# Colibri.net
KiCad netlist of a schematic drawn in Altium Designer
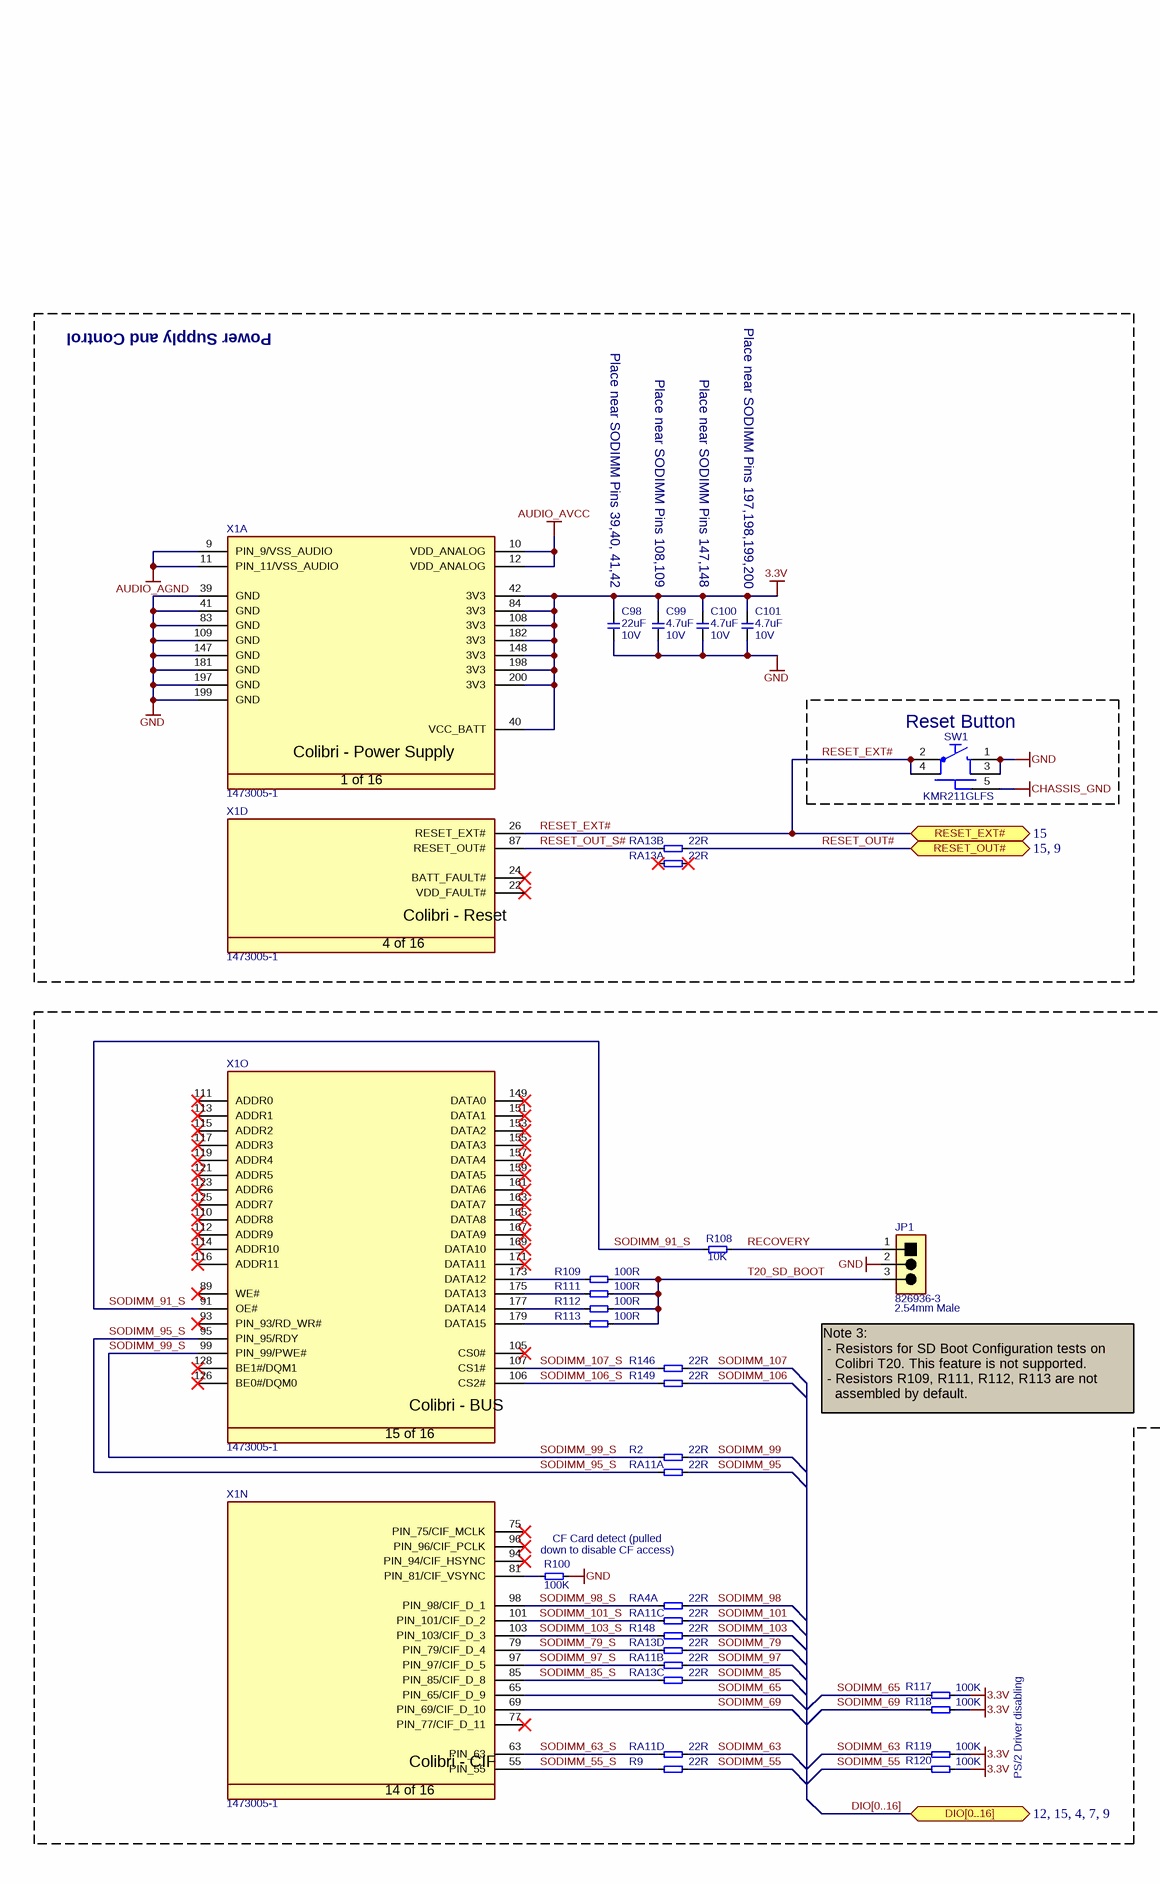
[diagram p0: Colibri.SchDoc, left]
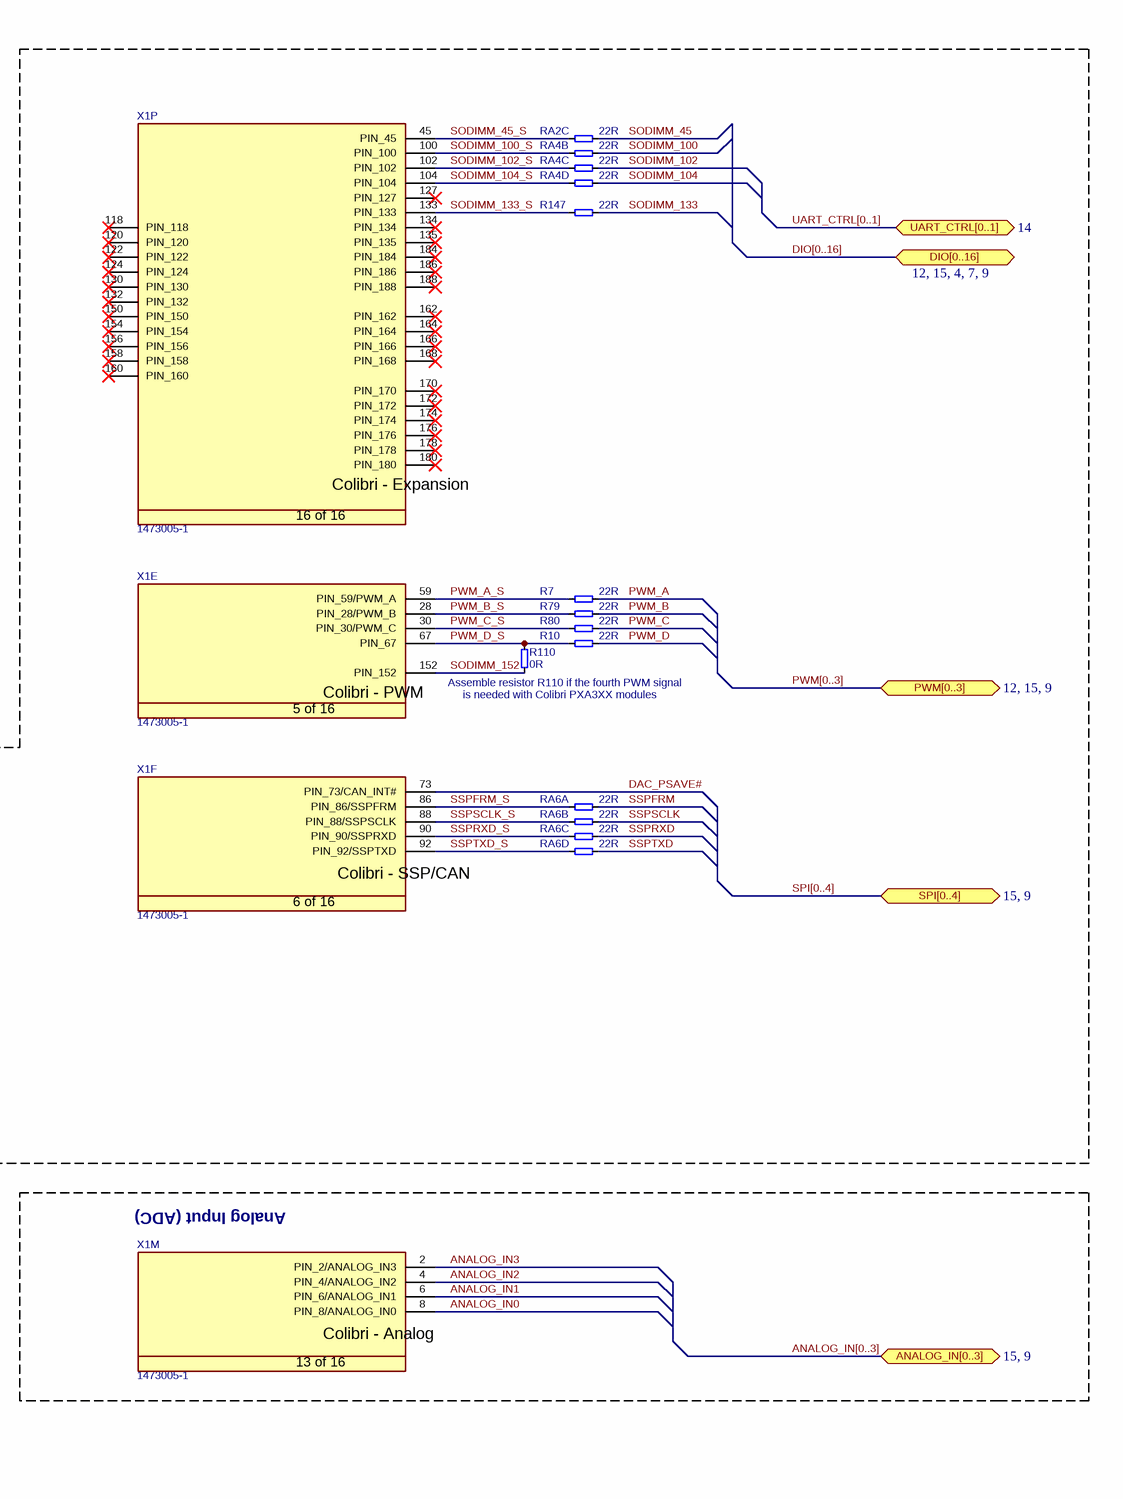
[diagram p1: Colibri.SchDoc, right]

(export (version "E")
  (design (tool "Eeschema 10.0.6"))
  (components
    (comp (ref "C98")
      (value "22uF")
      (footprint "T_CAPC0805X125N")
      (description "Capacitor Ceramic X5R 22uF 10V 20% 0805")
      (fields (field (name "TOLERANCE") "20%") (field (name "RATING") "10V"))
      (libsource (lib "Iris") (part "C-X5R-22uF-10V-20%-0805"))
    )
    (comp (ref "C99")
      (value "4.7uF")
      (footprint "T_CAPC0603X33N")
      (description "Capacitor Ceramic X5R 4.7uF 10V 10% 0603")
      (fields (field (name "TOLERANCE") "10%") (field (name "RATING") "10V"))
      (libsource (lib "Iris") (part "C-X5R-4.7uF-10V-10%-0603"))
    )
    (comp (ref "C100")
      (value "4.7uF")
      (footprint "T_CAPC0603X33N")
      (description "Capacitor Ceramic X5R 4.7uF 10V 10% 0603")
      (fields (field (name "TOLERANCE") "10%") (field (name "RATING") "10V"))
      (libsource (lib "Iris") (part "C-X5R-4.7uF-10V-10%-0603"))
    )
    (comp (ref "C101")
      (value "4.7uF")
      (footprint "T_CAPC0603X33N")
      (description "Capacitor Ceramic X5R 4.7uF 10V 10% 0603")
      (fields (field (name "TOLERANCE") "10%") (field (name "RATING") "10V"))
      (libsource (lib "Iris") (part "C-X5R-4.7uF-10V-10%-0603"))
    )
    (comp (ref "JP1")
      (value "826936-3")
      (footprint "T_TYCO_826936-3")
      (description "Jumper, 3-Pin")
      (fields (field (name "MANUFACTURER PART NO.") "826936-3"))
      (libsource (lib "Iris") (part "CON-Tyco-826936-3-1X3-2.54mm-JP"))
    )
    (comp (ref "R2")
      (value "22R")
      (footprint "RESC1005X40N")
      (description "Resistor 22 ohm 63mW 5% 0402")
      (fields (field (name "TOLERANCE") "5%"))
      (libsource (lib "Iris") (part "R-22R-63mW-5%-0402"))
    )
    (comp (ref "R7")
      (value "22R")
      (footprint "RESC1005X40N")
      (description "Resistor 22 ohm 63mW 5% 0402")
      (fields (field (name "TOLERANCE") "5%"))
      (libsource (lib "Iris") (part "R-22R-63mW-5%-0402"))
    )
    (comp (ref "R9")
      (value "22R")
      (footprint "RESC1005X40N")
      (description "Resistor 22 ohm 63mW 5% 0402")
      (fields (field (name "TOLERANCE") "5%"))
      (libsource (lib "Iris") (part "R-22R-63mW-5%-0402"))
    )
    (comp (ref "R10")
      (value "22R")
      (footprint "RESC1005X40N")
      (description "Resistor 22 ohm 63mW 5% 0402")
      (fields (field (name "TOLERANCE") "5%"))
      (libsource (lib "Iris") (part "R-22R-63mW-5%-0402"))
    )
    (comp (ref "R79")
      (value "22R")
      (footprint "RESC1005X40N")
      (description "Resistor 22 ohm 63mW 5% 0402")
      (fields (field (name "TOLERANCE") "5%"))
      (libsource (lib "Iris") (part "R-22R-63mW-5%-0402"))
    )
    (comp (ref "R80")
      (value "22R")
      (footprint "RESC1005X40N")
      (description "Resistor 22 ohm 63mW 5% 0402")
      (fields (field (name "TOLERANCE") "5%"))
      (libsource (lib "Iris") (part "R-22R-63mW-5%-0402"))
    )
    (comp (ref "R100")
      (value "100K")
      (footprint "RESC1005X40N")
      (description "Resistor 100 Kohm 63mW 5% 0402")
      (fields (field (name "TOLERANCE") "5%"))
      (libsource (lib "Iris") (part "R-100KR-63mW-5%-0402"))
    )
    (comp (ref "R108")
      (value "10K")
      (footprint "RESC1005X40N")
      (description "Resistor 10 Kohm 63mW 1% 0402")
      (fields (field (name "TOLERANCE") "1%"))
      (libsource (lib "Iris") (part "R-10KR-63mW-1%-0402"))
    )
    (comp (ref "R109")
      (value "100R")
      (footprint "T_RESC0603X30N")
      (description "Resistor 100 ohm 63mW 5% 0603")
      (fields (field (name "TOLERANCE") "5%"))
      (libsource (lib "Iris") (part "R-100R-63mW-5%-0603"))
    )
    (comp (ref "R110")
      (value "0R")
      (footprint "T_RESC0603X30N")
      (description "Resistor 0 ohm 63mW 5% 0603")
      (fields (field (name "TOLERANCE") "5%"))
      (libsource (lib "Iris") (part "R-0R-63mW-5%-0603"))
    )
    (comp (ref "R111")
      (value "100R")
      (footprint "T_RESC0603X30N")
      (description "Resistor 100 ohm 63mW 5% 0603")
      (fields (field (name "TOLERANCE") "5%"))
      (libsource (lib "Iris") (part "R-100R-63mW-5%-0603"))
    )
    (comp (ref "R112")
      (value "100R")
      (footprint "T_RESC0603X30N")
      (description "Resistor 100 ohm 63mW 5% 0603")
      (fields (field (name "TOLERANCE") "5%"))
      (libsource (lib "Iris") (part "R-100R-63mW-5%-0603"))
    )
    (comp (ref "R113")
      (value "100R")
      (footprint "T_RESC0603X30N")
      (description "Resistor 100 ohm 63mW 5% 0603")
      (fields (field (name "TOLERANCE") "5%"))
      (libsource (lib "Iris") (part "R-100R-63mW-5%-0603"))
    )
    (comp (ref "R117")
      (value "100K")
      (footprint "RESC1005X40N")
      (description "Resistor 100 Kohm 63mW 5% 0402")
      (fields (field (name "TOLERANCE") "5%"))
      (libsource (lib "Iris") (part "R-100KR-63mW-5%-0402"))
    )
    (comp (ref "R118")
      (value "100K")
      (footprint "RESC1005X40N")
      (description "Resistor 100 Kohm 63mW 5% 0402")
      (fields (field (name "TOLERANCE") "5%"))
      (libsource (lib "Iris") (part "R-100KR-63mW-5%-0402"))
    )
    (comp (ref "R119")
      (value "100K")
      (footprint "RESC1005X40N")
      (description "Resistor 100 Kohm 63mW 5% 0402")
      (fields (field (name "TOLERANCE") "5%"))
      (libsource (lib "Iris") (part "R-100KR-63mW-5%-0402"))
    )
    (comp (ref "R120")
      (value "100K")
      (footprint "RESC1005X40N")
      (description "Resistor 100 Kohm 63mW 5% 0402")
      (fields (field (name "TOLERANCE") "5%"))
      (libsource (lib "Iris") (part "R-100KR-63mW-5%-0402"))
    )
    (comp (ref "R146")
      (value "22R")
      (footprint "RESC1005X40N")
      (description "Resistor 22 ohm 63mW 5% 0402")
      (fields (field (name "TOLERANCE") "5%"))
      (libsource (lib "Iris") (part "R-22R-63mW-5%-0402"))
    )
    (comp (ref "R147")
      (value "22R")
      (footprint "RESC1005X40N")
      (description "Resistor 22 ohm 63mW 5% 0402")
      (fields (field (name "TOLERANCE") "5%"))
      (libsource (lib "Iris") (part "R-22R-63mW-5%-0402"))
    )
    (comp (ref "R148")
      (value "22R")
      (footprint "RESC1005X40N")
      (description "Resistor 22 ohm 63mW 5% 0402")
      (fields (field (name "TOLERANCE") "5%"))
      (libsource (lib "Iris") (part "R-22R-63mW-5%-0402"))
    )
    (comp (ref "R149")
      (value "22R")
      (footprint "RESC1005X40N")
      (description "Resistor 22 ohm 63mW 5% 0402")
      (fields (field (name "TOLERANCE") "5%"))
      (libsource (lib "Iris") (part "R-22R-63mW-5%-0402"))
    )
    (comp (ref "RA2")
      (value "22R")
      (footprint "T_Resistor_Array_X4")
      (description "Resistor Array 22 R 63mW 5% 1206")
      (fields (field (name "TOLERANCE") "5%"))
      (libsource (lib "Iris") (part "RA-22R-63mW-5%-1206-div"))
    )
    (comp (ref "RA4")
      (value "22R")
      (footprint "T_Resistor_Array_X4")
      (description "Resistor Array 22 R 63mW 5% 1206")
      (fields (field (name "TOLERANCE") "5%"))
      (libsource (lib "Iris") (part "RA-22R-63mW-5%-1206-div"))
    )
    (comp (ref "RA6")
      (value "22R")
      (footprint "T_Resistor_Array_X4")
      (description "Resistor Array 22 R 63mW 5% 1206")
      (fields (field (name "TOLERANCE") "5%"))
      (libsource (lib "Iris") (part "RA-22R-63mW-5%-1206-div"))
    )
    (comp (ref "RA11")
      (value "22R")
      (footprint "T_Resistor_Array_X4")
      (description "Resistor Array 22 R 63mW 5% 1206")
      (fields (field (name "TOLERANCE") "5%"))
      (libsource (lib "Iris") (part "RA-22R-63mW-5%-1206-div"))
    )
    (comp (ref "RA13")
      (value "22R")
      (footprint "T_Resistor_Array_X4")
      (description "Resistor Array 22 R 63mW 5% 1206")
      (fields (field (name "TOLERANCE") "5%"))
      (libsource (lib "Iris") (part "RA-22R-63mW-5%-1206-div"))
    )
    (comp (ref "SW1")
      (value "KMR211GLFS")
      (footprint "T_CnK_KMR211GLFS")
      (description "Power ON Switch")
      (libsource (lib "Iris") (part "SW_CnK-KMR211GLFS-1VA"))
    )
    (comp (ref "X1")
      (value "1473005-1")
      (footprint "T_Tyco_1473005-1")
      (description "SODIMM Connector")
      (fields (field (name "MANUFACTURER PART NO.") "1473005-1"))
      (libsource (lib "Iris") (part "CON-Tyco-1473005-1-200-0.6mm"))
    )
  )
  (nets
    (net (code "29") (name "/ANALOG_IN0") (class "Default")
      (node (ref "X1") (pin "8") (pinfunction "PIN_8/ANALOG_IN0_8") (pintype "passive"))
    )
    (net (code "30") (name "/ANALOG_IN1") (class "Default")
      (node (ref "X1") (pin "6") (pinfunction "PIN_6/ANALOG_IN1_6") (pintype "passive"))
    )
    (net (code "31") (name "/ANALOG_IN2") (class "Default")
      (node (ref "X1") (pin "4") (pinfunction "PIN_4/ANALOG_IN2_4") (pintype "passive"))
    )
    (net (code "32") (name "/ANALOG_IN3") (class "Default")
      (node (ref "X1") (pin "2") (pinfunction "PIN_2/ANALOG_IN3_2") (pintype "passive"))
    )
    (net (code "34") (name "/DAC_PSAVE#") (class "Default")
      (node (ref "X1") (pin "73") (pinfunction "PIN_73/CAN_INT#_73") (pintype "passive"))
    )
    (net (code "37") (name "/PWM_A") (class "Default")
      (node (ref "R7") (pin "2") (pinfunction "2_2") (pintype "passive"))
    )
    (net (code "38") (name "/PWM_A_S") (class "Default")
      (node (ref "R7") (pin "1") (pinfunction "1_1") (pintype "passive"))
      (node (ref "X1") (pin "59") (pinfunction "PIN_59/PWM_A_59") (pintype "passive"))
    )
    (net (code "39") (name "/PWM_B") (class "Default")
      (node (ref "R79") (pin "2") (pinfunction "2_2") (pintype "passive"))
    )
    (net (code "40") (name "/PWM_B_S") (class "Default")
      (node (ref "R79") (pin "1") (pinfunction "1_1") (pintype "passive"))
      (node (ref "X1") (pin "28") (pinfunction "PIN_28/PWM_B_28") (pintype "passive"))
    )
    (net (code "41") (name "/PWM_C") (class "Default")
      (node (ref "R80") (pin "2") (pinfunction "2_2") (pintype "passive"))
    )
    (net (code "42") (name "/PWM_C_S") (class "Default")
      (node (ref "R80") (pin "1") (pinfunction "1_1") (pintype "passive"))
      (node (ref "X1") (pin "30") (pinfunction "PIN_30/PWM_C_30") (pintype "passive"))
    )
    (net (code "43") (name "/PWM_D") (class "Default")
      (node (ref "R10") (pin "2") (pinfunction "2_2") (pintype "passive"))
    )
    (net (code "44") (name "/PWM_D_S") (class "Default")
      (node (ref "R10") (pin "1") (pinfunction "1_1") (pintype "passive"))
      (node (ref "R110") (pin "1") (pinfunction "1_1") (pintype "passive"))
      (node (ref "X1") (pin "67") (pinfunction "PIN_67_67") (pintype "passive"))
    )
    (net (code "45") (name "/RECOVERY") (class "Default")
      (node (ref "JP1") (pin "1") (pinfunction "1_1") (pintype "passive"))
      (node (ref "R108") (pin "2") (pinfunction "2_2") (pintype "passive"))
    )
    (net (code "46") (name "/RESET_EXT#") (class "Default")
      (node (ref "SW1") (pin "2") (pinfunction "2_2") (pintype "passive"))
      (node (ref "SW1") (pin "4") (pinfunction "4_4") (pintype "passive"))
      (node (ref "X1") (pin "26") (pinfunction "RESET_EXT#_26") (pintype "passive"))
    )
    (net (code "47") (name "/RESET_OUT#") (class "Default")
      (node (ref "RA13") (pin "6") (pinfunction "6_6") (pintype "passive"))
    )
    (net (code "48") (name "/RESET_OUT_S#") (class "Default")
      (node (ref "RA13") (pin "2") (pinfunction "2_2") (pintype "passive"))
      (node (ref "X1") (pin "87") (pinfunction "RESET_OUT#_87") (pintype "passive"))
    )
    (net (code "49") (name "/SODIMM_45") (class "Default")
      (node (ref "RA2") (pin "7") (pinfunction "7_7") (pintype "passive"))
    )
    (net (code "50") (name "/SODIMM_45_S") (class "Default")
      (node (ref "RA2") (pin "3") (pinfunction "3_3") (pintype "passive"))
      (node (ref "X1") (pin "45") (pinfunction "PIN_45_45") (pintype "passive"))
    )
    (net (code "51") (name "/SODIMM_55") (class "Default")
      (node (ref "R120") (pin "2") (pinfunction "2_2") (pintype "passive"))
      (node (ref "R9") (pin "2") (pinfunction "2_2") (pintype "passive"))
    )
    (net (code "52") (name "/SODIMM_55_S") (class "Default")
      (node (ref "R9") (pin "1") (pinfunction "1_1") (pintype "passive"))
      (node (ref "X1") (pin "55") (pinfunction "PIN_55_55") (pintype "passive"))
    )
    (net (code "53") (name "/SODIMM_63") (class "Default")
      (node (ref "R119") (pin "2") (pinfunction "2_2") (pintype "passive"))
      (node (ref "RA11") (pin "8") (pinfunction "8_8") (pintype "passive"))
    )
    (net (code "54") (name "/SODIMM_63_S") (class "Default")
      (node (ref "RA11") (pin "4") (pinfunction "4_4") (pintype "passive"))
      (node (ref "X1") (pin "63") (pinfunction "PIN_63_63") (pintype "passive"))
    )
    (net (code "55") (name "/SODIMM_65") (class "Default")
      (node (ref "R117") (pin "2") (pinfunction "2_2") (pintype "passive"))
      (node (ref "X1") (pin "65") (pinfunction "PIN_65/CIF_D_9_65") (pintype "passive"))
    )
    (net (code "56") (name "/SODIMM_69") (class "Default")
      (node (ref "R118") (pin "2") (pinfunction "2_2") (pintype "passive"))
      (node (ref "X1") (pin "69") (pinfunction "PIN_69/CIF_D_10_69") (pintype "passive"))
    )
    (net (code "57") (name "/SODIMM_79") (class "Default")
      (node (ref "RA13") (pin "8") (pinfunction "8_8") (pintype "passive"))
    )
    (net (code "58") (name "/SODIMM_79_S") (class "Default")
      (node (ref "RA13") (pin "4") (pinfunction "4_4") (pintype "passive"))
      (node (ref "X1") (pin "79") (pinfunction "PIN_79/CIF_D_4_79") (pintype "passive"))
    )
    (net (code "59") (name "/SODIMM_85") (class "Default")
      (node (ref "RA13") (pin "7") (pinfunction "7_7") (pintype "passive"))
    )
    (net (code "60") (name "/SODIMM_85_S") (class "Default")
      (node (ref "RA13") (pin "3") (pinfunction "3_3") (pintype "passive"))
      (node (ref "X1") (pin "85") (pinfunction "PIN_85/CIF_D_8_85") (pintype "passive"))
    )
    (net (code "61") (name "/SODIMM_91_S") (class "Default")
      (node (ref "R108") (pin "1") (pinfunction "1_1") (pintype "passive"))
      (node (ref "X1") (pin "91") (pinfunction "OE#_91") (pintype "passive"))
    )
    (net (code "62") (name "/SODIMM_95") (class "Default")
      (node (ref "RA11") (pin "5") (pinfunction "5_5") (pintype "passive"))
    )
    (net (code "63") (name "/SODIMM_95_S") (class "Default")
      (node (ref "RA11") (pin "1") (pinfunction "1_1") (pintype "passive"))
      (node (ref "X1") (pin "95") (pinfunction "PIN_95/RDY_95") (pintype "passive"))
    )
    (net (code "64") (name "/SODIMM_97") (class "Default")
      (node (ref "RA11") (pin "6") (pinfunction "6_6") (pintype "passive"))
    )
    (net (code "65") (name "/SODIMM_97_S") (class "Default")
      (node (ref "RA11") (pin "2") (pinfunction "2_2") (pintype "passive"))
      (node (ref "X1") (pin "97") (pinfunction "PIN_97/CIF_D_5_97") (pintype "passive"))
    )
    (net (code "66") (name "/SODIMM_98") (class "Default")
      (node (ref "RA4") (pin "5") (pinfunction "5_5") (pintype "passive"))
    )
    (net (code "67") (name "/SODIMM_98_S") (class "Default")
      (node (ref "RA4") (pin "1") (pinfunction "1_1") (pintype "passive"))
      (node (ref "X1") (pin "98") (pinfunction "PIN_98/CIF_D_1_98") (pintype "passive"))
    )
    (net (code "68") (name "/SODIMM_99") (class "Default")
      (node (ref "R2") (pin "2") (pinfunction "2_2") (pintype "passive"))
    )
    (net (code "69") (name "/SODIMM_99_S") (class "Default")
      (node (ref "R2") (pin "1") (pinfunction "1_1") (pintype "passive"))
      (node (ref "X1") (pin "99") (pinfunction "PIN_99/PWE#_99") (pintype "passive"))
    )
    (net (code "70") (name "/SODIMM_100") (class "Default")
      (node (ref "RA4") (pin "6") (pinfunction "6_6") (pintype "passive"))
    )
    (net (code "71") (name "/SODIMM_100_S") (class "Default")
      (node (ref "RA4") (pin "2") (pinfunction "2_2") (pintype "passive"))
      (node (ref "X1") (pin "100") (pinfunction "PIN_100_100") (pintype "passive"))
    )
    (net (code "72") (name "/SODIMM_101") (class "Default")
      (node (ref "RA11") (pin "7") (pinfunction "7_7") (pintype "passive"))
    )
    (net (code "73") (name "/SODIMM_101_S") (class "Default")
      (node (ref "RA11") (pin "3") (pinfunction "3_3") (pintype "passive"))
      (node (ref "X1") (pin "101") (pinfunction "PIN_101/CIF_D_2_101") (pintype "passive"))
    )
    (net (code "74") (name "/SODIMM_102") (class "Default")
      (node (ref "RA4") (pin "7") (pinfunction "7_7") (pintype "passive"))
    )
    (net (code "75") (name "/SODIMM_102_S") (class "Default")
      (node (ref "RA4") (pin "3") (pinfunction "3_3") (pintype "passive"))
      (node (ref "X1") (pin "102") (pinfunction "PIN_102_102") (pintype "passive"))
    )
    (net (code "76") (name "/SODIMM_103") (class "Default")
      (node (ref "R148") (pin "2") (pinfunction "2_2") (pintype "passive"))
    )
    (net (code "77") (name "/SODIMM_103_S") (class "Default")
      (node (ref "R148") (pin "1") (pinfunction "1_1") (pintype "passive"))
      (node (ref "X1") (pin "103") (pinfunction "PIN_103/CIF_D_3_103") (pintype "passive"))
    )
    (net (code "78") (name "/SODIMM_104") (class "Default")
      (node (ref "RA4") (pin "8") (pinfunction "8_8") (pintype "passive"))
    )
    (net (code "79") (name "/SODIMM_104_S") (class "Default")
      (node (ref "RA4") (pin "4") (pinfunction "4_4") (pintype "passive"))
      (node (ref "X1") (pin "104") (pinfunction "PIN_104_104") (pintype "passive"))
    )
    (net (code "80") (name "/SODIMM_106") (class "Default")
      (node (ref "R149") (pin "2") (pinfunction "2_2") (pintype "passive"))
    )
    (net (code "81") (name "/SODIMM_106_S") (class "Default")
      (node (ref "R149") (pin "1") (pinfunction "1_1") (pintype "passive"))
      (node (ref "X1") (pin "106") (pinfunction "CS2#_106") (pintype "passive"))
    )
    (net (code "82") (name "/SODIMM_107") (class "Default")
      (node (ref "R146") (pin "2") (pinfunction "2_2") (pintype "passive"))
    )
    (net (code "83") (name "/SODIMM_107_S") (class "Default")
      (node (ref "R146") (pin "1") (pinfunction "1_1") (pintype "passive"))
      (node (ref "X1") (pin "107") (pinfunction "CS1#_107") (pintype "passive"))
    )
    (net (code "84") (name "/SODIMM_133") (class "Default")
      (node (ref "R147") (pin "2") (pinfunction "2_2") (pintype "passive"))
    )
    (net (code "85") (name "/SODIMM_133_S") (class "Default")
      (node (ref "R147") (pin "1") (pinfunction "1_1") (pintype "passive"))
      (node (ref "X1") (pin "133") (pinfunction "PIN_133_133") (pintype "passive"))
    )
    (net (code "86") (name "/SODIMM_152") (class "Default")
      (node (ref "R110") (pin "2") (pinfunction "2_2") (pintype "passive"))
      (node (ref "X1") (pin "152") (pinfunction "PIN_152_152") (pintype "passive"))
    )
    (net (code "88") (name "/SSPFRM") (class "Default")
      (node (ref "RA6") (pin "5") (pinfunction "5_5") (pintype "passive"))
    )
    (net (code "89") (name "/SSPFRM_S") (class "Default")
      (node (ref "RA6") (pin "1") (pinfunction "1_1") (pintype "passive"))
      (node (ref "X1") (pin "86") (pinfunction "PIN_86/SSPFRM_86") (pintype "passive"))
    )
    (net (code "90") (name "/SSPRXD") (class "Default")
      (node (ref "RA6") (pin "7") (pinfunction "7_7") (pintype "passive"))
    )
    (net (code "91") (name "/SSPRXD_S") (class "Default")
      (node (ref "RA6") (pin "3") (pinfunction "3_3") (pintype "passive"))
      (node (ref "X1") (pin "90") (pinfunction "PIN_90/SSPRXD_90") (pintype "passive"))
    )
    (net (code "92") (name "/SSPSCLK") (class "Default")
      (node (ref "RA6") (pin "6") (pinfunction "6_6") (pintype "passive"))
    )
    (net (code "93") (name "/SSPSCLK_S") (class "Default")
      (node (ref "RA6") (pin "2") (pinfunction "2_2") (pintype "passive"))
      (node (ref "X1") (pin "88") (pinfunction "PIN_88/SSPSCLK_88") (pintype "passive"))
    )
    (net (code "94") (name "/SSPTXD") (class "Default")
      (node (ref "RA6") (pin "8") (pinfunction "8_8") (pintype "passive"))
    )
    (net (code "95") (name "/SSPTXD_S") (class "Default")
      (node (ref "RA6") (pin "4") (pinfunction "4_4") (pintype "passive"))
      (node (ref "X1") (pin "92") (pinfunction "PIN_92/SSPTXD_92") (pintype "passive"))
    )
    (net (code "96") (name "/T20_SD_BOOT") (class "Default")
      (node (ref "JP1") (pin "3") (pinfunction "3_3") (pintype "passive"))
      (node (ref "R109") (pin "1") (pinfunction "1_1") (pintype "passive"))
      (node (ref "R111") (pin "1") (pinfunction "1_1") (pintype "passive"))
      (node (ref "R112") (pin "1") (pinfunction "1_1") (pintype "passive"))
      (node (ref "R113") (pin "1") (pinfunction "1_1") (pintype "passive"))
    )
    (net (code "98") (name "3.3V") (class "Default")
      (node (ref "C100") (pin "1") (pinfunction "1_1") (pintype "passive"))
      (node (ref "C101") (pin "1") (pinfunction "1_1") (pintype "passive"))
      (node (ref "C98") (pin "2") (pinfunction "2_2") (pintype "passive"))
      (node (ref "C99") (pin "1") (pinfunction "1_1") (pintype "passive"))
      (node (ref "R117") (pin "1") (pinfunction "1_1") (pintype "passive"))
      (node (ref "R118") (pin "1") (pinfunction "1_1") (pintype "passive"))
      (node (ref "R119") (pin "1") (pinfunction "1_1") (pintype "passive"))
      (node (ref "R120") (pin "1") (pinfunction "1_1") (pintype "passive"))
      (node (ref "X1") (pin "108") (pinfunction "3V3_108") (pintype "passive"))
      (node (ref "X1") (pin "148") (pinfunction "3V3_148") (pintype "passive"))
      (node (ref "X1") (pin "182") (pinfunction "3V3_182") (pintype "power_in"))
      (node (ref "X1") (pin "198") (pinfunction "3V3_198") (pintype "power_in"))
      (node (ref "X1") (pin "200") (pinfunction "3V3_200") (pintype "power_in"))
      (node (ref "X1") (pin "40") (pinfunction "VCC_BATT_40") (pintype "power_in"))
      (node (ref "X1") (pin "42") (pinfunction "3V3_42") (pintype "power_in"))
      (node (ref "X1") (pin "84") (pinfunction "3V3_84") (pintype "power_in"))
    )
    (net (code "99") (name "AUDIO_AGND") (class "Default")
      (node (ref "X1") (pin "11") (pinfunction "PIN_11/VSS_AUDIO_11") (pintype "passive"))
      (node (ref "X1") (pin "9") (pinfunction "PIN_9/VSS_AUDIO_9") (pintype "passive"))
    )
    (net (code "100") (name "AUDIO_AVCC") (class "Default")
      (node (ref "X1") (pin "10") (pinfunction "VDD_ANALOG_10") (pintype "passive"))
      (node (ref "X1") (pin "12") (pinfunction "VDD_ANALOG_12") (pintype "passive"))
    )
    (net (code "101") (name "CHASSIS_GND") (class "Default")
      (node (ref "SW1") (pin "5") (pinfunction "5_5") (pintype "passive"))
    )
    (net (code "102") (name "GND") (class "Default")
      (node (ref "C100") (pin "2") (pinfunction "2_2") (pintype "passive"))
      (node (ref "C101") (pin "2") (pinfunction "2_2") (pintype "passive"))
      (node (ref "C98") (pin "1") (pinfunction "1_1") (pintype "passive"))
      (node (ref "C99") (pin "2") (pinfunction "2_2") (pintype "passive"))
      (node (ref "JP1") (pin "2") (pinfunction "2_2") (pintype "passive"))
      (node (ref "R100") (pin "1") (pinfunction "1_1") (pintype "passive"))
      (node (ref "SW1") (pin "1") (pinfunction "1_1") (pintype "passive"))
      (node (ref "SW1") (pin "3") (pinfunction "3_3") (pintype "passive"))
      (node (ref "X1") (pin "109") (pinfunction "GND_109") (pintype "power_in"))
      (node (ref "X1") (pin "147") (pinfunction "GND_147") (pintype "power_in"))
      (node (ref "X1") (pin "181") (pinfunction "GND_181") (pintype "power_in"))
      (node (ref "X1") (pin "197") (pinfunction "GND_197") (pintype "power_in"))
      (node (ref "X1") (pin "199") (pinfunction "GND_199") (pintype "power_in"))
      (node (ref "X1") (pin "39") (pinfunction "GND_39") (pintype "power_in"))
      (node (ref "X1") (pin "41") (pinfunction "GND_41") (pintype "power_in"))
      (node (ref "X1") (pin "83") (pinfunction "GND_83") (pintype "power_in"))
    )
    (net (code "103") (name "Net-(X1N-PIN_81{slash}CIF_VSYNC)") (class "Default")
      (node (ref "R100") (pin "2") (pinfunction "2_2") (pintype "passive"))
      (node (ref "X1") (pin "81") (pinfunction "PIN_81/CIF_VSYNC_81") (pintype "passive"))
    )
    (net (code "104") (name "Net-(X1O-DATA12)") (class "Default")
      (node (ref "R109") (pin "2") (pinfunction "2_2") (pintype "passive"))
      (node (ref "X1") (pin "173") (pinfunction "DATA12_173") (pintype "passive"))
    )
    (net (code "105") (name "Net-(X1O-DATA13)") (class "Default")
      (node (ref "R111") (pin "2") (pinfunction "2_2") (pintype "passive"))
      (node (ref "X1") (pin "175") (pinfunction "DATA13_175") (pintype "passive"))
    )
    (net (code "106") (name "Net-(X1O-DATA14)") (class "Default")
      (node (ref "R112") (pin "2") (pinfunction "2_2") (pintype "passive"))
      (node (ref "X1") (pin "177") (pinfunction "DATA14_177") (pintype "passive"))
    )
    (net (code "107") (name "Net-(X1O-DATA15)") (class "Default")
      (node (ref "R113") (pin "2") (pinfunction "2_2") (pintype "passive"))
      (node (ref "X1") (pin "179") (pinfunction "DATA15_179") (pintype "passive"))
    )
    (net (code "108") (name "unconnected-(RA13-Pad1)") (class "Default")
      (node (ref "RA13") (pin "1") (pinfunction "1_1") (pintype "passive+no_connect"))
    )
    (net (code "109") (name "unconnected-(RA13-Pad5)") (class "Default")
      (node (ref "RA13") (pin "5") (pinfunction "5_5") (pintype "passive+no_connect"))
    )
    (net (code "110") (name "unconnected-(X1D-BATT_FAULT#-Pad24)") (class "Default")
      (node (ref "X1") (pin "24") (pinfunction "BATT_FAULT#_24") (pintype "passive+no_connect"))
    )
    (net (code "111") (name "unconnected-(X1D-VDD_FAULT#-Pad22)") (class "Default")
      (node (ref "X1") (pin "22") (pinfunction "VDD_FAULT#_22") (pintype "passive+no_connect"))
    )
    (net (code "112") (name "unconnected-(X1N-PIN_75{slash}CIF_MCLK-Pad75)") (class "Default")
      (node (ref "X1") (pin "75") (pinfunction "PIN_75/CIF_MCLK_75") (pintype "passive+no_connect"))
    )
    (net (code "113") (name "unconnected-(X1N-PIN_77{slash}CIF_D_11-Pad77)") (class "Default")
      (node (ref "X1") (pin "77") (pinfunction "PIN_77/CIF_D_11_77") (pintype "passive+no_connect"))
    )
    (net (code "114") (name "unconnected-(X1N-PIN_94{slash}CIF_HSYNC-Pad94)") (class "Default")
      (node (ref "X1") (pin "94") (pinfunction "PIN_94/CIF_HSYNC_94") (pintype "passive+no_connect"))
    )
    (net (code "115") (name "unconnected-(X1N-PIN_96{slash}CIF_PCLK-Pad96)") (class "Default")
      (node (ref "X1") (pin "96") (pinfunction "PIN_96/CIF_PCLK_96") (pintype "passive+no_connect"))
    )
    (net (code "116") (name "unconnected-(X1O-ADDR0-Pad111)") (class "Default")
      (node (ref "X1") (pin "111") (pinfunction "ADDR0_111") (pintype "passive+no_connect"))
    )
    (net (code "117") (name "unconnected-(X1O-ADDR1-Pad113)") (class "Default")
      (node (ref "X1") (pin "113") (pinfunction "ADDR1_113") (pintype "passive+no_connect"))
    )
    (net (code "118") (name "unconnected-(X1O-ADDR2-Pad115)") (class "Default")
      (node (ref "X1") (pin "115") (pinfunction "ADDR2_115") (pintype "passive+no_connect"))
    )
    (net (code "119") (name "unconnected-(X1O-ADDR3-Pad117)") (class "Default")
      (node (ref "X1") (pin "117") (pinfunction "ADDR3_117") (pintype "passive+no_connect"))
    )
    (net (code "120") (name "unconnected-(X1O-ADDR4-Pad119)") (class "Default")
      (node (ref "X1") (pin "119") (pinfunction "ADDR4_119") (pintype "passive+no_connect"))
    )
    (net (code "121") (name "unconnected-(X1O-ADDR5-Pad121)") (class "Default")
      (node (ref "X1") (pin "121") (pinfunction "ADDR5_121") (pintype "passive+no_connect"))
    )
    (net (code "122") (name "unconnected-(X1O-ADDR6-Pad123)") (class "Default")
      (node (ref "X1") (pin "123") (pinfunction "ADDR6_123") (pintype "passive+no_connect"))
    )
    (net (code "123") (name "unconnected-(X1O-ADDR7-Pad125)") (class "Default")
      (node (ref "X1") (pin "125") (pinfunction "ADDR7_125") (pintype "passive+no_connect"))
    )
    (net (code "124") (name "unconnected-(X1O-ADDR8-Pad110)") (class "Default")
      (node (ref "X1") (pin "110") (pinfunction "ADDR8_110") (pintype "passive+no_connect"))
    )
    (net (code "125") (name "unconnected-(X1O-ADDR9-Pad112)") (class "Default")
      (node (ref "X1") (pin "112") (pinfunction "ADDR9_112") (pintype "passive+no_connect"))
    )
    (net (code "126") (name "unconnected-(X1O-ADDR10-Pad114)") (class "Default")
      (node (ref "X1") (pin "114") (pinfunction "ADDR10_114") (pintype "passive+no_connect"))
    )
    (net (code "127") (name "unconnected-(X1O-ADDR11-Pad116)") (class "Default")
      (node (ref "X1") (pin "116") (pinfunction "ADDR11_116") (pintype "passive+no_connect"))
    )
    (net (code "128") (name "unconnected-(X1O-BE0#{slash}DQM0-Pad126)") (class "Default")
      (node (ref "X1") (pin "126") (pinfunction "BE0#/DQM0_126") (pintype "passive+no_connect"))
    )
    (net (code "129") (name "unconnected-(X1O-BE1#{slash}DQM1-Pad128)") (class "Default")
      (node (ref "X1") (pin "128") (pinfunction "BE1#/DQM1_128") (pintype "passive+no_connect"))
    )
    (net (code "130") (name "unconnected-(X1O-CS0#-Pad105)") (class "Default")
      (node (ref "X1") (pin "105") (pinfunction "CS0#_105") (pintype "passive+no_connect"))
    )
    (net (code "131") (name "unconnected-(X1O-DATA0-Pad149)") (class "Default")
      (node (ref "X1") (pin "149") (pinfunction "DATA0_149") (pintype "passive+no_connect"))
    )
    (net (code "132") (name "unconnected-(X1O-DATA1-Pad151)") (class "Default")
      (node (ref "X1") (pin "151") (pinfunction "DATA1_151") (pintype "passive+no_connect"))
    )
    (net (code "133") (name "unconnected-(X1O-DATA2-Pad153)") (class "Default")
      (node (ref "X1") (pin "153") (pinfunction "DATA2_153") (pintype "passive+no_connect"))
    )
    (net (code "134") (name "unconnected-(X1O-DATA3-Pad155)") (class "Default")
      (node (ref "X1") (pin "155") (pinfunction "DATA3_155") (pintype "passive+no_connect"))
    )
    (net (code "135") (name "unconnected-(X1O-DATA4-Pad157)") (class "Default")
      (node (ref "X1") (pin "157") (pinfunction "DATA4_157") (pintype "passive+no_connect"))
    )
    (net (code "136") (name "unconnected-(X1O-DATA5-Pad159)") (class "Default")
      (node (ref "X1") (pin "159") (pinfunction "DATA5_159") (pintype "passive+no_connect"))
    )
    (net (code "137") (name "unconnected-(X1O-DATA6-Pad161)") (class "Default")
      (node (ref "X1") (pin "161") (pinfunction "DATA6_161") (pintype "passive+no_connect"))
    )
    (net (code "138") (name "unconnected-(X1O-DATA7-Pad163)") (class "Default")
      (node (ref "X1") (pin "163") (pinfunction "DATA7_163") (pintype "passive+no_connect"))
    )
    (net (code "139") (name "unconnected-(X1O-DATA8-Pad165)") (class "Default")
      (node (ref "X1") (pin "165") (pinfunction "DATA8_165") (pintype "passive+no_connect"))
    )
    (net (code "140") (name "unconnected-(X1O-DATA9-Pad167)") (class "Default")
      (node (ref "X1") (pin "167") (pinfunction "DATA9_167") (pintype "passive+no_connect"))
    )
    (net (code "141") (name "unconnected-(X1O-DATA10-Pad169)") (class "Default")
      (node (ref "X1") (pin "169") (pinfunction "DATA10_169") (pintype "passive+no_connect"))
    )
    (net (code "142") (name "unconnected-(X1O-DATA11-Pad171)") (class "Default")
      (node (ref "X1") (pin "171") (pinfunction "DATA11_171") (pintype "passive+no_connect"))
    )
    (net (code "143") (name "unconnected-(X1O-PIN_93{slash}RD_WR#-Pad93)") (class "Default")
      (node (ref "X1") (pin "93") (pinfunction "PIN_93/RD_WR#_93") (pintype "passive+no_connect"))
    )
    (net (code "144") (name "unconnected-(X1O-WE#-Pad89)") (class "Default")
      (node (ref "X1") (pin "89") (pinfunction "WE#_89") (pintype "passive+no_connect"))
    )
    (net (code "145") (name "unconnected-(X1P-PIN_118-Pad118)") (class "Default")
      (node (ref "X1") (pin "118") (pinfunction "PIN_118_118") (pintype "passive+no_connect"))
    )
    (net (code "146") (name "unconnected-(X1P-PIN_120-Pad120)") (class "Default")
      (node (ref "X1") (pin "120") (pinfunction "PIN_120_120") (pintype "passive+no_connect"))
    )
    (net (code "147") (name "unconnected-(X1P-PIN_122-Pad122)") (class "Default")
      (node (ref "X1") (pin "122") (pinfunction "PIN_122_122") (pintype "passive+no_connect"))
    )
    (net (code "148") (name "unconnected-(X1P-PIN_124-Pad124)") (class "Default")
      (node (ref "X1") (pin "124") (pinfunction "PIN_124_124") (pintype "passive+no_connect"))
    )
    (net (code "149") (name "unconnected-(X1P-PIN_127-Pad127)") (class "Default")
      (node (ref "X1") (pin "127") (pinfunction "PIN_127_127") (pintype "passive+no_connect"))
    )
    (net (code "150") (name "unconnected-(X1P-PIN_130-Pad130)") (class "Default")
      (node (ref "X1") (pin "130") (pinfunction "PIN_130_130") (pintype "passive+no_connect"))
    )
    (net (code "151") (name "unconnected-(X1P-PIN_132-Pad132)") (class "Default")
      (node (ref "X1") (pin "132") (pinfunction "PIN_132_132") (pintype "passive+no_connect"))
    )
    (net (code "152") (name "unconnected-(X1P-PIN_134-Pad134)") (class "Default")
      (node (ref "X1") (pin "134") (pinfunction "PIN_134_134") (pintype "passive+no_connect"))
    )
    (net (code "153") (name "unconnected-(X1P-PIN_135-Pad135)") (class "Default")
      (node (ref "X1") (pin "135") (pinfunction "PIN_135_135") (pintype "passive+no_connect"))
    )
    (net (code "154") (name "unconnected-(X1P-PIN_150-Pad150)") (class "Default")
      (node (ref "X1") (pin "150") (pinfunction "PIN_150_150") (pintype "passive+no_connect"))
    )
    (net (code "155") (name "unconnected-(X1P-PIN_154-Pad154)") (class "Default")
      (node (ref "X1") (pin "154") (pinfunction "PIN_154_154") (pintype "passive+no_connect"))
    )
    (net (code "156") (name "unconnected-(X1P-PIN_156-Pad156)") (class "Default")
      (node (ref "X1") (pin "156") (pinfunction "PIN_156_156") (pintype "passive+no_connect"))
    )
    (net (code "157") (name "unconnected-(X1P-PIN_158-Pad158)") (class "Default")
      (node (ref "X1") (pin "158") (pinfunction "PIN_158_158") (pintype "passive+no_connect"))
    )
    (net (code "158") (name "unconnected-(X1P-PIN_160-Pad160)") (class "Default")
      (node (ref "X1") (pin "160") (pinfunction "PIN_160_160") (pintype "passive+no_connect"))
    )
    (net (code "159") (name "unconnected-(X1P-PIN_162-Pad162)") (class "Default")
      (node (ref "X1") (pin "162") (pinfunction "PIN_162_162") (pintype "passive+no_connect"))
    )
    (net (code "160") (name "unconnected-(X1P-PIN_164-Pad164)") (class "Default")
      (node (ref "X1") (pin "164") (pinfunction "PIN_164_164") (pintype "passive+no_connect"))
    )
    (net (code "161") (name "unconnected-(X1P-PIN_166-Pad166)") (class "Default")
      (node (ref "X1") (pin "166") (pinfunction "PIN_166_166") (pintype "passive+no_connect"))
    )
    (net (code "162") (name "unconnected-(X1P-PIN_168-Pad168)") (class "Default")
      (node (ref "X1") (pin "168") (pinfunction "PIN_168_168") (pintype "passive+no_connect"))
    )
    (net (code "163") (name "unconnected-(X1P-PIN_170-Pad170)") (class "Default")
      (node (ref "X1") (pin "170") (pinfunction "PIN_170_170") (pintype "passive+no_connect"))
    )
    (net (code "164") (name "unconnected-(X1P-PIN_172-Pad172)") (class "Default")
      (node (ref "X1") (pin "172") (pinfunction "PIN_172_172") (pintype "passive+no_connect"))
    )
    (net (code "165") (name "unconnected-(X1P-PIN_174-Pad174)") (class "Default")
      (node (ref "X1") (pin "174") (pinfunction "PIN_174_174") (pintype "passive+no_connect"))
    )
    (net (code "166") (name "unconnected-(X1P-PIN_176-Pad176)") (class "Default")
      (node (ref "X1") (pin "176") (pinfunction "PIN_176_176") (pintype "passive+no_connect"))
    )
    (net (code "167") (name "unconnected-(X1P-PIN_178-Pad178)") (class "Default")
      (node (ref "X1") (pin "178") (pinfunction "PIN_178_178") (pintype "passive+no_connect"))
    )
    (net (code "168") (name "unconnected-(X1P-PIN_180-Pad180)") (class "Default")
      (node (ref "X1") (pin "180") (pinfunction "PIN_180_180") (pintype "passive+no_connect"))
    )
    (net (code "169") (name "unconnected-(X1P-PIN_184-Pad184)") (class "Default")
      (node (ref "X1") (pin "184") (pinfunction "PIN_184_184") (pintype "passive+no_connect"))
    )
    (net (code "170") (name "unconnected-(X1P-PIN_186-Pad186)") (class "Default")
      (node (ref "X1") (pin "186") (pinfunction "PIN_186_186") (pintype "passive+no_connect"))
    )
    (net (code "171") (name "unconnected-(X1P-PIN_188-Pad188)") (class "Default")
      (node (ref "X1") (pin "188") (pinfunction "PIN_188_188") (pintype "passive+no_connect"))
    )
  )
)
